# Schmetic.net
KiCad netlist of a schematic drawn in Altium Designer
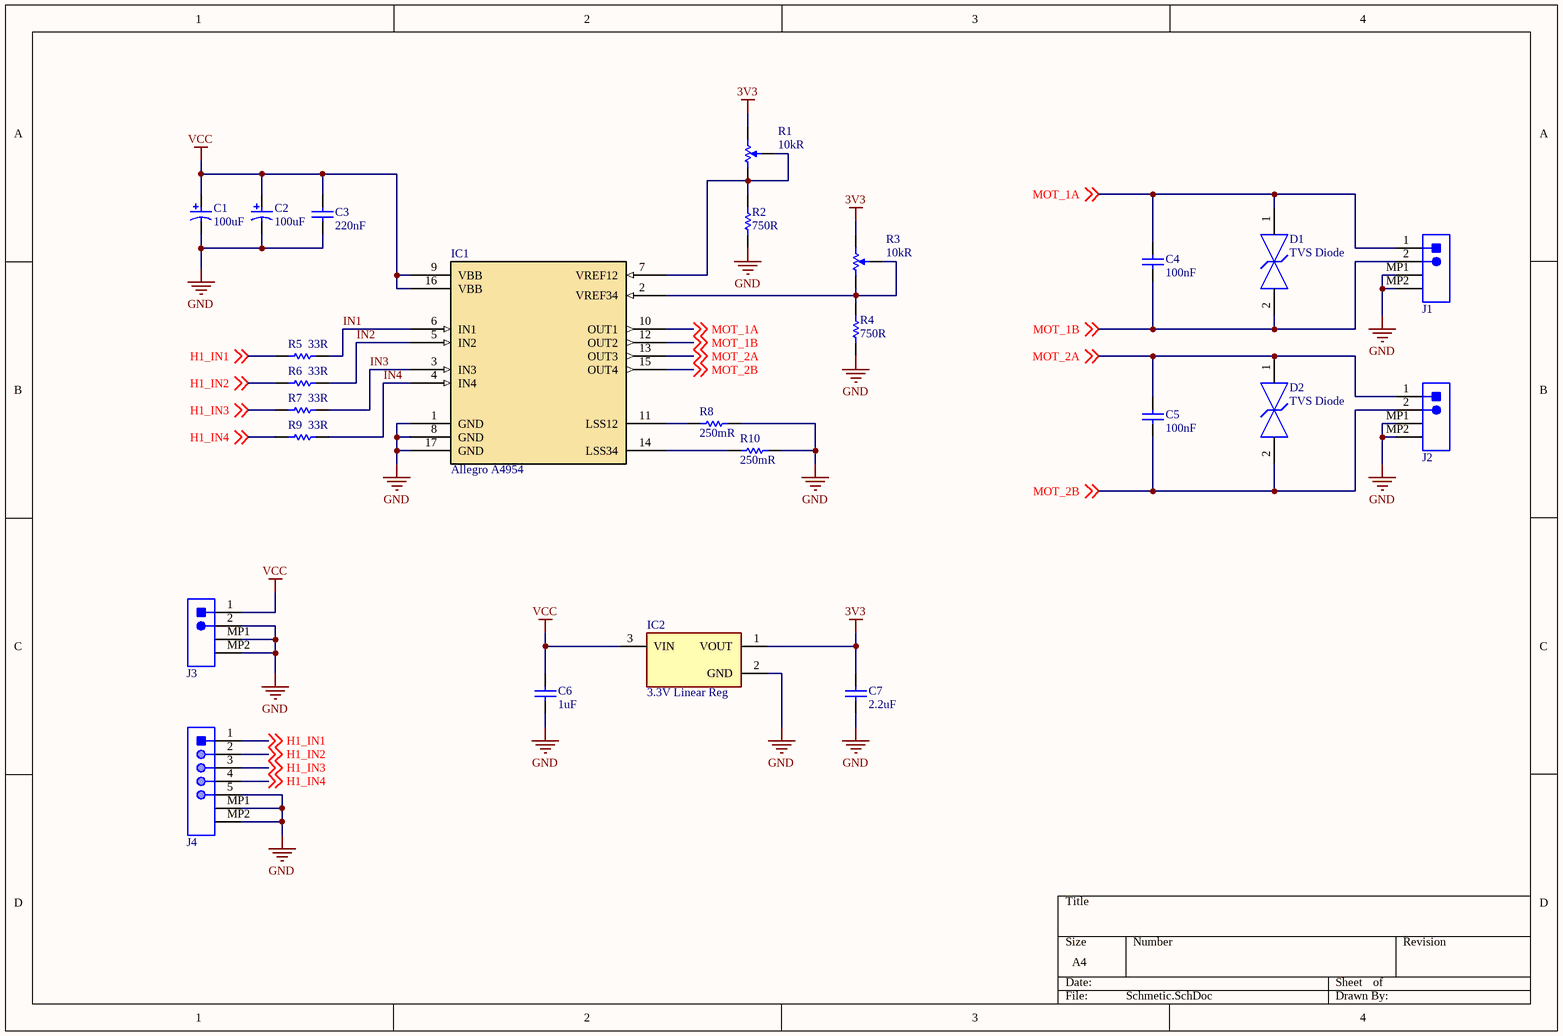
[diagram p0: Schmetic.SchDoc]

(export (version "E")
  (design (tool "Eeschema 10.0.6"))
  (components
    (comp (ref "C1")
      (value "100uF")
      (footprint "NIC-UWT1H101MNL1GS_N")
      (description "100uF 50 V dc Aluminium Electrolytic Capacitor; WT Series 1000h 8 (Dia.) x 10mm")
      (fields
        (field (name "MANUFACTURER") "Nichicon")
        (field (name "MANUFACTURER PART NUMBER") "UWT1H101MNL1GS")
      )
      (libsource (lib "SchLib") (part "100uF"))
    )
    (comp (ref "C2")
      (value "100uF")
      (footprint "NIC-UWT1H101MNL1GS_N")
      (description "100uF 50 V dc Aluminium Electrolytic Capacitor; WT Series 1000h 8 (Dia.) x 10mm")
      (fields
        (field (name "MANUFACTURER") "Nichicon")
        (field (name "MANUFACTURER PART NUMBER") "UWT1H101MNL1GS")
      )
      (libsource (lib "SchLib") (part "100uF"))
    )
    (comp (ref "C3")
      (value "220nF")
      (footprint "CAPC1005X55N")
      (description "TAIYO YUDEN - UMK105BJ224KV-F - CAPACITOR, MLCC, X5R, 0.22UF, 50V, 0402, FULL REEL")
      (fields
        (field (name "MANUFACTURER") "Taiyo Yuden")
        (field (name "MANUFACTURER PART NUMBER") "UMK105BJ224KV-F")
      )
      (libsource (lib "SchLib") (part "220nF"))
    )
    (comp (ref "C4")
      (value "100nF")
      (footprint "CAPC1005X60X30NL05T10")
      (fields
        (field (name "MANUFACTURER") "KEMET")
        (field (name "MANUFACTURER PART NUMBER") "C0402C104K8PACTU")
        (field (name "TOLERANCE") "10%")
      )
      (libsource (lib "SchLib") (part "100nF"))
    )
    (comp (ref "C5")
      (value "100nF")
      (footprint "CAPC1005X60X30NL05T10")
      (fields
        (field (name "MANUFACTURER") "KEMET")
        (field (name "MANUFACTURER PART NUMBER") "C0402C104K8PACTU")
        (field (name "TOLERANCE") "10%")
      )
      (libsource (lib "SchLib") (part "100nF"))
    )
    (comp (ref "C6")
      (value "1uF")
      (footprint "CAP_CL10_SAM")
      (description "Cap Ceramic 1uF 50V X5R 10% SMD 0603 85C Cardboard T/R")
      (fields
        (field (name "MANUFACTURER") "Samsung")
        (field (name "MANUFACTURER PART NUMBER") "CL10A105KB8NNNC")
      )
      (libsource (lib "SchLib") (part "1uF"))
    )
    (comp (ref "C7")
      (value "2.2uF")
      (footprint "CAPC1608X90N")
      (fields
        (field (name "MANUFACTURER") "Samsung")
        (field (name "MANUFACTURER PART NUMBER") "CL10A225KP8NNNC")
        (field (name "TOLERANCE") "10%")
      )
      (libsource (lib "SchLib") (part "2.2uF"))
    )
    (comp (ref "D1")
      (value "TVS Diode")
      (footprint "FP-SMAJ-CA-MFG")
      (fields (field (name "MANUFACTURER") "Littelfuse") (field (name "MANUFACTURER PART NUMBER") "SMAJ36CA"))
      (libsource (lib "SchLib") (part "TVS Diode"))
    )
    (comp (ref "D2")
      (value "TVS Diode")
      (footprint "FP-SMAJ-CA-MFG")
      (fields (field (name "MANUFACTURER") "Littelfuse") (field (name "MANUFACTURER PART NUMBER") "SMAJ36CA"))
      (libsource (lib "SchLib") (part "TVS Diode"))
    )
    (comp (ref "IC1")
      (value "Allegro A4954")
      (footprint "TSSOP-16_ALM")
      (description "IC MOTOR DRIVER PAR 16TSSOP")
      (fields
        (field (name "MANUFACTURER") "Allegro MicroSystems")
        (field (name "MANUFACTURER PART NUMBER") "A4954ELPTR-T")
      )
      (libsource (lib "SchLib") (part "Allegro A4954"))
    )
    (comp (ref "IC2")
      (value "3.3V Linear Reg")
      (footprint "FP-SOT89-MFG")
      (description "IC REG LINEAR 3.3V 150MA SOT89")
      (fields
        (field (name "MANUFACTURER") "Diodes")
        (field (name "MANUFACTURER PART NUMBER") "AP7381-33Y-13")
      )
      (libsource (lib "SchLib") (part "3.3V Linear Reg"))
    )
    (comp (ref "J1")
      (value "2 Pin Header")
      (footprint "JST-BM02B-GHS-TBT_V")
      (description "CONN HEADER SMD 2POS 1.25MM")
      (fields
        (field (name "MANUFACTURER") "JST")
        (field (name "MANUFACTURER PART NUMBER") "BM02B-GHS-TBT(LF)(SN)(N)")
      )
      (libsource (lib "SchLib") (part "2 Pin Header"))
    )
    (comp (ref "J2")
      (value "2 Pin Header")
      (footprint "JST-BM02B-GHS-TBT_V")
      (description "CONN HEADER SMD 2POS 1.25MM")
      (fields
        (field (name "MANUFACTURER") "JST")
        (field (name "MANUFACTURER PART NUMBER") "BM02B-GHS-TBT(LF)(SN)(N)")
      )
      (libsource (lib "SchLib") (part "2 Pin Header"))
    )
    (comp (ref "J3")
      (value "2 Pin Header")
      (footprint "JST-BM02B-GHS-TBT_V")
      (description "CONN HEADER SMD 2POS 1.25MM")
      (fields
        (field (name "MANUFACTURER") "JST")
        (field (name "MANUFACTURER PART NUMBER") "BM02B-GHS-TBT(LF)(SN)(N)")
      )
      (libsource (lib "") (part "2 Pin Header_1"))
    )
    (comp (ref "J4")
      (value "5 Pin Header")
      (footprint "JST-BM05B-GHS-TBT_V")
      (libsource (lib "SchLib") (part "5 Pin Header"))
    )
    (comp (ref "R1")
      (value "10kR")
      (footprint "BOUR-TC33X-2_V")
      (description "Res Trimmer 10K Ohm 25% 1/10W 1(Elec)/1(Mech)Turn (3 X 3.8mm) Foot Print SMD Embossed T/R")
      (fields (field (name "MANUFACTURER") "Bourns") (field (name "MANUFACTURER PART NUMBER") "TC33X-2-103E"))
      (libsource (lib "SchLib") (part "10kR"))
    )
    (comp (ref "R2")
      (value "750R")
      (footprint "RESC1005X40X25NL05T05")
      (fields
        (field (name "MANUFACTURER") "Panasonic")
        (field (name "MANUFACTURER PART NUMBER") "ERJ2RKF7500X")
        (field (name "TOLERANCE") "1%")
      )
      (libsource (lib "SchLib") (part "750R"))
    )
    (comp (ref "R3")
      (value "10kR")
      (footprint "BOUR-TC33X-2_V")
      (description "Res Trimmer 10K Ohm 25% 1/10W 1(Elec)/1(Mech)Turn (3 X 3.8mm) Foot Print SMD Embossed T/R")
      (fields (field (name "MANUFACTURER") "Bourns") (field (name "MANUFACTURER PART NUMBER") "TC33X-2-103E"))
      (libsource (lib "SchLib") (part "10kR"))
    )
    (comp (ref "R4")
      (value "750R")
      (footprint "RESC1005X40X25NL05T05")
      (fields
        (field (name "MANUFACTURER") "Panasonic")
        (field (name "MANUFACTURER PART NUMBER") "ERJ2RKF7500X")
        (field (name "TOLERANCE") "1%")
      )
      (libsource (lib "SchLib") (part "750R"))
    )
    (comp (ref "R5")
      (value "33R")
      (footprint "RESC1005X40X25NL05T05")
      (description "GLOVE, POLYAMIDE, L/FREE, PU, SIZE 6 - More Details")
      (fields
        (field (name "MANUFACTURER") "Panasonic")
        (field (name "MANUFACTURER PART NUMBER") "ERJ-2GEJ330X")
      )
      (libsource (lib "SchLib") (part "33R"))
    )
    (comp (ref "R6")
      (value "33R")
      (footprint "RESC1005X40X25NL05T05")
      (description "GLOVE, POLYAMIDE, L/FREE, PU, SIZE 6 - More Details")
      (fields
        (field (name "MANUFACTURER") "Panasonic")
        (field (name "MANUFACTURER PART NUMBER") "ERJ-2GEJ330X")
      )
      (libsource (lib "SchLib") (part "33R"))
    )
    (comp (ref "R7")
      (value "33R")
      (footprint "RESC1005X40X25NL05T05")
      (description "GLOVE, POLYAMIDE, L/FREE, PU, SIZE 6 - More Details")
      (fields
        (field (name "MANUFACTURER") "Panasonic")
        (field (name "MANUFACTURER PART NUMBER") "ERJ-2GEJ330X")
      )
      (libsource (lib "SchLib") (part "33R"))
    )
    (comp (ref "R8")
      (value "250mR")
      (footprint "RESC3015X65N")
      (description "Res Thick Film 1206 250m Ohm 1% 1/2W 100ppm/C Molded SMD Paper T/R")
      (fields
        (field (name "MANUFACTURER") "Stackpole Electronics")
        (field (name "MANUFACTURER PART NUMBER") "CSR1206FKR250")
      )
      (libsource (lib "SchLib") (part "250mR"))
    )
    (comp (ref "R9")
      (value "33R")
      (footprint "RESC1005X40X25NL05T05")
      (description "GLOVE, POLYAMIDE, L/FREE, PU, SIZE 6 - More Details")
      (fields
        (field (name "MANUFACTURER") "Panasonic")
        (field (name "MANUFACTURER PART NUMBER") "ERJ-2GEJ330X")
      )
      (libsource (lib "SchLib") (part "33R"))
    )
    (comp (ref "R10")
      (value "250mR")
      (footprint "RESC3015X65N")
      (description "Res Thick Film 1206 250m Ohm 1% 1/2W 100ppm/C Molded SMD Paper T/R")
      (fields
        (field (name "MANUFACTURER") "Stackpole Electronics")
        (field (name "MANUFACTURER PART NUMBER") "CSR1206FKR250")
      )
      (libsource (lib "SchLib") (part "250mR"))
    )
  )
  (nets
    (net (code "1") (name "/IN1") (class "Default")
      (node (ref "IC1") (pin "6") (pinfunction "IN1_6") (pintype "input"))
      (node (ref "R5") (pin "2") (pinfunction "2_2") (pintype "passive"))
    )
    (net (code "2") (name "/IN2") (class "Default")
      (node (ref "IC1") (pin "5") (pinfunction "IN2_5") (pintype "input"))
      (node (ref "R6") (pin "2") (pinfunction "2_2") (pintype "passive"))
    )
    (net (code "3") (name "/IN3") (class "Default")
      (node (ref "IC1") (pin "3") (pinfunction "IN3_3") (pintype "input"))
      (node (ref "R7") (pin "2") (pinfunction "2_2") (pintype "passive"))
    )
    (net (code "4") (name "/IN4") (class "Default")
      (node (ref "IC1") (pin "4") (pinfunction "IN4_4") (pintype "input"))
      (node (ref "R9") (pin "2") (pinfunction "2_2") (pintype "passive"))
    )
    (net (code "5") (name "3V3") (class "Default")
      (node (ref "C7") (pin "2") (pinfunction "2_2") (pintype "passive"))
      (node (ref "IC2") (pin "1") (pinfunction "VOUT_1") (pintype "power_in"))
      (node (ref "R1") (pin "3") (pinfunction "3_3") (pintype "passive"))
      (node (ref "R3") (pin "3") (pinfunction "3_3") (pintype "passive"))
    )
    (net (code "6") (name "GND") (class "Default")
      (node (ref "C1") (pin "2") (pinfunction "2_2") (pintype "passive"))
      (node (ref "C2") (pin "2") (pinfunction "2_2") (pintype "passive"))
      (node (ref "C3") (pin "1") (pinfunction "1_1") (pintype "passive"))
      (node (ref "C6") (pin "1") (pinfunction "1_1") (pintype "passive"))
      (node (ref "C7") (pin "1") (pinfunction "1_1") (pintype "passive"))
      (node (ref "IC1") (pin "1") (pinfunction "GND_1") (pintype "power_in"))
      (node (ref "IC1") (pin "17") (pinfunction "GND_17") (pintype "passive"))
      (node (ref "IC1") (pin "8") (pinfunction "GND_8") (pintype "power_in"))
      (node (ref "IC2") (pin "2") (pinfunction "GND_2") (pintype "power_in"))
      (node (ref "J1") (pin "MP1") (pinfunction "MP1_MP1") (pintype "passive"))
      (node (ref "J1") (pin "MP2") (pinfunction "MP2_MP2") (pintype "passive"))
      (node (ref "J2") (pin "MP1") (pinfunction "MP1_MP1") (pintype "passive"))
      (node (ref "J2") (pin "MP2") (pinfunction "MP2_MP2") (pintype "passive"))
      (node (ref "J3") (pin "2") (pinfunction "2_2") (pintype "passive"))
      (node (ref "J3") (pin "MP1") (pinfunction "MP1_MP1") (pintype "passive"))
      (node (ref "J3") (pin "MP2") (pinfunction "MP2_MP2") (pintype "passive"))
      (node (ref "J4") (pin "5") (pinfunction "5_5") (pintype "passive"))
      (node (ref "J4") (pin "MP1") (pinfunction "MP1_MP1") (pintype "passive"))
      (node (ref "J4") (pin "MP2") (pinfunction "MP2_MP2") (pintype "passive"))
      (node (ref "R10") (pin "2") (pinfunction "2_2") (pintype "passive"))
      (node (ref "R2") (pin "1") (pinfunction "1_1") (pintype "passive"))
      (node (ref "R4") (pin "1") (pinfunction "1_1") (pintype "passive"))
      (node (ref "R8") (pin "2") (pinfunction "2_2") (pintype "passive"))
    )
    (net (code "7") (name "H1_IN1") (class "Default")
      (node (ref "J4") (pin "1") (pinfunction "1_1") (pintype "passive"))
      (node (ref "R5") (pin "1") (pinfunction "1_1") (pintype "passive"))
    )
    (net (code "8") (name "H1_IN2") (class "Default")
      (node (ref "J4") (pin "2") (pinfunction "2_2") (pintype "passive"))
      (node (ref "R6") (pin "1") (pinfunction "1_1") (pintype "passive"))
    )
    (net (code "9") (name "H1_IN3") (class "Default")
      (node (ref "J4") (pin "3") (pinfunction "3_3") (pintype "passive"))
      (node (ref "R7") (pin "1") (pinfunction "1_1") (pintype "passive"))
    )
    (net (code "10") (name "H1_IN4") (class "Default")
      (node (ref "J4") (pin "4") (pinfunction "4_4") (pintype "passive"))
      (node (ref "R9") (pin "1") (pinfunction "1_1") (pintype "passive"))
    )
    (net (code "11") (name "MOT_1A") (class "Default")
      (node (ref "C4") (pin "2") (pinfunction "2_2") (pintype "passive"))
      (node (ref "D1") (pin "1") (pinfunction "1_1") (pintype "passive"))
      (node (ref "IC1") (pin "10") (pinfunction "OUT1_10") (pintype "output"))
      (node (ref "J1") (pin "1") (pinfunction "1_1") (pintype "passive"))
    )
    (net (code "12") (name "MOT_1B") (class "Default")
      (node (ref "C4") (pin "1") (pinfunction "1_1") (pintype "passive"))
      (node (ref "D1") (pin "2") (pinfunction "2_2") (pintype "passive"))
      (node (ref "IC1") (pin "12") (pinfunction "OUT2_12") (pintype "output"))
      (node (ref "J1") (pin "2") (pinfunction "2_2") (pintype "passive"))
    )
    (net (code "13") (name "MOT_2A") (class "Default")
      (node (ref "C5") (pin "1") (pinfunction "1_1") (pintype "passive"))
      (node (ref "D2") (pin "1") (pinfunction "1_1") (pintype "passive"))
      (node (ref "IC1") (pin "13") (pinfunction "OUT3_13") (pintype "output"))
      (node (ref "J2") (pin "1") (pinfunction "1_1") (pintype "passive"))
    )
    (net (code "14") (name "MOT_2B") (class "Default")
      (node (ref "C5") (pin "2") (pinfunction "2_2") (pintype "passive"))
      (node (ref "D2") (pin "2") (pinfunction "2_2") (pintype "passive"))
      (node (ref "IC1") (pin "15") (pinfunction "OUT4_15") (pintype "output"))
      (node (ref "J2") (pin "2") (pinfunction "2_2") (pintype "passive"))
    )
    (net (code "15") (name "Net-(IC1-LSS12)") (class "Default")
      (node (ref "IC1") (pin "11") (pinfunction "LSS12_11") (pintype "passive"))
      (node (ref "R8") (pin "1") (pinfunction "1_1") (pintype "passive"))
    )
    (net (code "16") (name "Net-(IC1-LSS34)") (class "Default")
      (node (ref "IC1") (pin "14") (pinfunction "LSS34_14") (pintype "passive"))
      (node (ref "R10") (pin "1") (pinfunction "1_1") (pintype "passive"))
    )
    (net (code "17") (name "Net-(IC1-VREF12)") (class "Default")
      (node (ref "IC1") (pin "7") (pinfunction "VREF12_7") (pintype "input"))
      (node (ref "R1") (pin "1") (pinfunction "1_1") (pintype "passive"))
      (node (ref "R1") (pin "2") (pinfunction "2_2") (pintype "passive"))
      (node (ref "R2") (pin "2") (pinfunction "2_2") (pintype "passive"))
    )
    (net (code "18") (name "Net-(IC1-VREF34)") (class "Default")
      (node (ref "IC1") (pin "2") (pinfunction "VREF34_2") (pintype "input"))
      (node (ref "R3") (pin "1") (pinfunction "1_1") (pintype "passive"))
      (node (ref "R3") (pin "2") (pinfunction "2_2") (pintype "passive"))
      (node (ref "R4") (pin "2") (pinfunction "2_2") (pintype "passive"))
    )
    (net (code "19") (name "VCC") (class "Default")
      (node (ref "C1") (pin "1") (pinfunction "1_1") (pintype "passive"))
      (node (ref "C2") (pin "1") (pinfunction "1_1") (pintype "passive"))
      (node (ref "C3") (pin "2") (pinfunction "2_2") (pintype "passive"))
      (node (ref "C6") (pin "2") (pinfunction "2_2") (pintype "passive"))
      (node (ref "IC1") (pin "16") (pinfunction "VBB_16") (pintype "power_in"))
      (node (ref "IC1") (pin "9") (pinfunction "VBB_9") (pintype "power_in"))
      (node (ref "IC2") (pin "3") (pinfunction "VIN_3") (pintype "power_in"))
      (node (ref "J3") (pin "1") (pinfunction "1_1") (pintype "passive"))
    )
  )
)
